# untitled.net
KiCad netlist of a schematic drawn in EAGLE
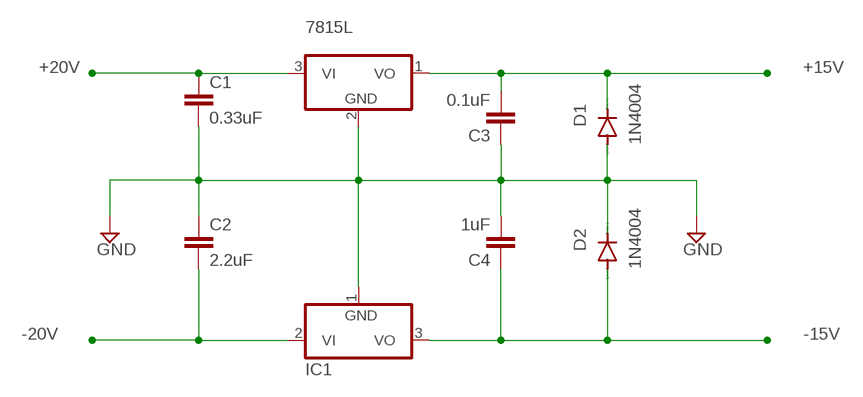
[diagram p0: schematic, sheet 1]

(export (version "E")
  (design (tool "Eeschema 10.0.6"))
  (components
    (comp (ref "C1")
      (value "0.33uF")
      (footprint "eagle-import:C2.5-3")
      (libsource (lib "eagle-import") (part "C2,5-3"))
    )
    (comp (ref "C2")
      (value "2.2uF")
      (footprint "eagle-import:C2.5-3")
      (libsource (lib "eagle-import") (part "C2,5-3"))
    )
    (comp (ref "C3")
      (value "0.1uF")
      (footprint "eagle-import:C2.5-3")
      (libsource (lib "eagle-import") (part "C2,5-3"))
    )
    (comp (ref "C4")
      (value "1uF")
      (footprint "eagle-import:C2.5-3")
      (libsource (lib "eagle-import") (part "C2,5-3"))
    )
    (comp (ref "D1")
      (value "1N4004")
      (footprint "eagle-import:DO41-10")
      (libsource (lib "eagle-import") (part "1N4004"))
    )
    (comp (ref "D2")
      (value "1N4004")
      (footprint "eagle-import:DO41-10")
      (libsource (lib "eagle-import") (part "1N4004"))
    )
    (comp (ref "IC1")
      (value "-15v")
      (footprint "eagle-import:TO92")
      (libsource (lib "eagle-import") (part "79L15"))
    )
    (comp (ref "LM7815")
      (value "7815L")
      (footprint "eagle-import:TO92")
      (libsource (lib "eagle-import") (part "78L15"))
    )
  )
  (nets
    (net (code "1") (name "/+15V") (class "Default")
      (node (ref "C3") (pin "2") (pinfunction "2_2") (pintype "passive"))
      (node (ref "D1") (pin "C") (pinfunction "C_C") (pintype "passive"))
      (node (ref "LM7815") (pin "1") (pinfunction "VO_1") (pintype "passive"))
    )
    (net (code "2") (name "/+20V") (class "Default")
      (node (ref "C1") (pin "1") (pinfunction "1_1") (pintype "passive"))
      (node (ref "LM7815") (pin "3") (pinfunction "VI_3") (pintype "input"))
    )
    (net (code "3") (name "/-15V") (class "Default")
      (node (ref "C4") (pin "1") (pinfunction "1_1") (pintype "passive"))
      (node (ref "D2") (pin "A") (pinfunction "A_A") (pintype "passive"))
      (node (ref "IC1") (pin "3") (pinfunction "VO_3") (pintype "passive"))
    )
    (net (code "4") (name "/-20V") (class "Default")
      (node (ref "C2") (pin "2") (pinfunction "2_2") (pintype "passive"))
      (node (ref "IC1") (pin "2") (pinfunction "VI_2") (pintype "input"))
    )
    (net (code "5") (name "GND") (class "Default")
      (node (ref "C1") (pin "2") (pinfunction "2_2") (pintype "passive"))
      (node (ref "C2") (pin "1") (pinfunction "1_1") (pintype "passive"))
      (node (ref "C3") (pin "1") (pinfunction "1_1") (pintype "passive"))
      (node (ref "C4") (pin "2") (pinfunction "2_2") (pintype "passive"))
      (node (ref "D1") (pin "A") (pinfunction "A_A") (pintype "passive"))
      (node (ref "D2") (pin "C") (pinfunction "C_C") (pintype "passive"))
      (node (ref "IC1") (pin "1") (pinfunction "GND_1") (pintype "passive"))
      (node (ref "LM7815") (pin "2") (pinfunction "GND_2") (pintype "passive"))
    )
  )
)
